# uDC_module.net
KiCad netlist of a schematic drawn in EAGLE
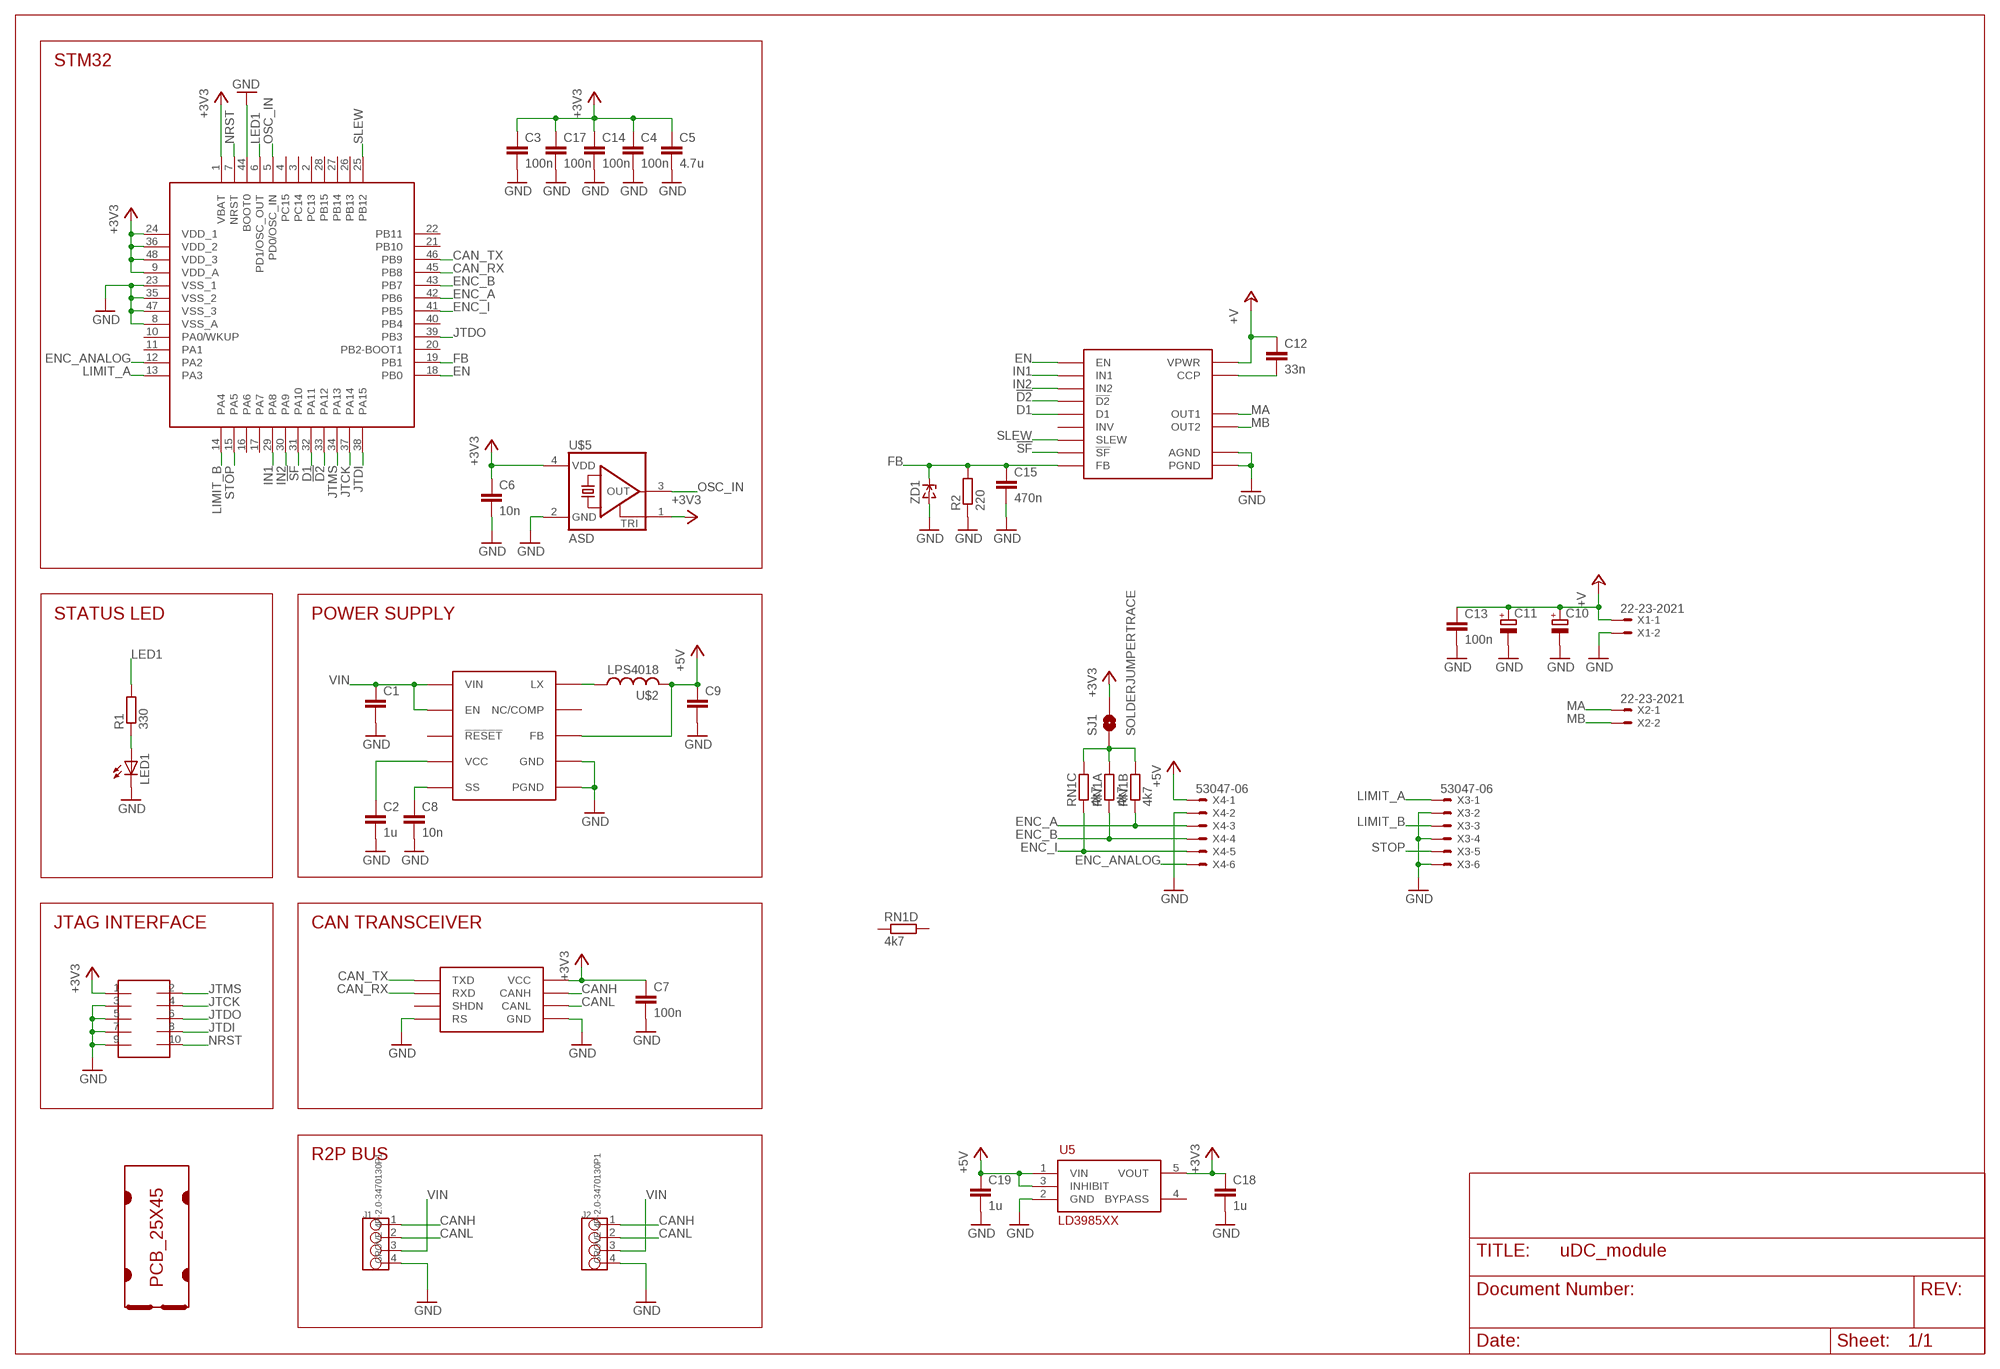
[diagram p0: schematic, sheet 1]

(export (version "E")
  (design (tool "Eeschema 10.0.6"))
  (components
    (comp (ref "C1")
      (value "C-EUC1206")
      (footprint "eagle-import:C1206")
      (libsource (lib "eagle-import") (part "C-EUC1206"))
    )
    (comp (ref "C2")
      (value "1u")
      (footprint "eagle-import:C0603")
      (libsource (lib "eagle-import") (part "C-EUC0603"))
    )
    (comp (ref "C3")
      (value "100n")
      (footprint "eagle-import:C0603")
      (libsource (lib "eagle-import") (part "C-EUC0603"))
    )
    (comp (ref "C4")
      (value "100n")
      (footprint "eagle-import:C0603")
      (libsource (lib "eagle-import") (part "C-EUC0603"))
    )
    (comp (ref "C5")
      (value "4.7u")
      (footprint "eagle-import:C0805")
      (libsource (lib "eagle-import") (part "C-EUC0805"))
    )
    (comp (ref "C6")
      (value "10n")
      (footprint "eagle-import:C0603")
      (libsource (lib "eagle-import") (part "C-EUC0603"))
    )
    (comp (ref "C7")
      (value "100n")
      (footprint "eagle-import:C0603")
      (libsource (lib "eagle-import") (part "C-EUC0603"))
    )
    (comp (ref "C8")
      (value "10n")
      (footprint "eagle-import:C0603")
      (libsource (lib "eagle-import") (part "C-EUC0603"))
    )
    (comp (ref "C9")
      (value "C-EUC0805")
      (footprint "eagle-import:C0805")
      (libsource (lib "eagle-import") (part "C-EUC0805"))
    )
    (comp (ref "C10")
      (value "CPOL-EUD")
      (footprint "eagle-import:PANASONIC_D")
      (libsource (lib "eagle-import") (part "CPOL-EUD"))
    )
    (comp (ref "C11")
      (value "CPOL-EUD")
      (footprint "eagle-import:PANASONIC_D")
      (libsource (lib "eagle-import") (part "CPOL-EUD"))
    )
    (comp (ref "C12")
      (value "33n")
      (footprint "eagle-import:C0603")
      (libsource (lib "eagle-import") (part "C-EUC0603"))
    )
    (comp (ref "C13")
      (value "100n")
      (footprint "eagle-import:C0603")
      (libsource (lib "eagle-import") (part "C-EUC0603"))
    )
    (comp (ref "C14")
      (value "100n")
      (footprint "eagle-import:C0603")
      (libsource (lib "eagle-import") (part "C-EUC0603"))
    )
    (comp (ref "C15")
      (value "470n")
      (footprint "eagle-import:C0603")
      (libsource (lib "eagle-import") (part "C-EUC0603"))
    )
    (comp (ref "C17")
      (value "100n")
      (footprint "eagle-import:C0603")
      (libsource (lib "eagle-import") (part "C-EUC0603"))
    )
    (comp (ref "C18")
      (value "1u")
      (footprint "eagle-import:C0603")
      (libsource (lib "eagle-import") (part "C-EUC0603"))
    )
    (comp (ref "C19")
      (value "1u")
      (footprint "eagle-import:C0603")
      (libsource (lib "eagle-import") (part "C-EUC0603"))
    )
    (comp (ref "J1")
      (value "GROVE-4P-2.0-3470130P1")
      (footprint "eagle-import:4P-2.0")
      (libsource (lib "eagle-import") (part "GROVE-4P-2.0-3470130P1"))
    )
    (comp (ref "J2")
      (value "GROVE-4P-2.0-3470130P1")
      (footprint "eagle-import:4P-2.0")
      (libsource (lib "eagle-import") (part "GROVE-4P-2.0-3470130P1"))
    )
    (comp (ref "LED1")
      (value "LEDCHIPLED_0805")
      (footprint "eagle-import:CHIPLED_0805")
      (libsource (lib "eagle-import") (part "LEDCHIPLED_0805"))
    )
    (comp (ref "R1")
      (value "330")
      (footprint "eagle-import:R0603")
      (libsource (lib "eagle-import") (part "R-EU_R0603"))
    )
    (comp (ref "R2")
      (value "220")
      (footprint "eagle-import:R0603")
      (libsource (lib "eagle-import") (part "R-EU_R0603"))
    )
    (comp (ref "RN1")
      (value "4k7")
      (footprint "eagle-import:RN8P-4R-CRA06S")
      (libsource (lib "eagle-import") (part "RESISTOR_ARRAY_4"))
    )
    (comp (ref "SJ1")
      (value "SOLDERJUMPERTRACE")
      (footprint "eagle-import:SJ_2S-TRACE")
      (libsource (lib "eagle-import") (part "SOLDERJUMPERTRACE"))
    )
    (comp (ref "SOT1")
      (value "MAX3051EKA")
      (footprint "eagle-import:SOT23-8L")
      (libsource (lib "eagle-import") (part "MAX3051EKA"))
    )
    (comp (ref "U$1")
      (value "PCB_25X45")
      (footprint "eagle-import:25X45")
      (libsource (lib "eagle-import") (part "PCB_25X45"))
    )
    (comp (ref "U$2")
      (value "LPS4018")
      (footprint "eagle-import:LPS4018")
      (libsource (lib "eagle-import") (part "LPS4018"))
    )
    (comp (ref "U$3")
      (value "MAX17501")
      (footprint "eagle-import:TDFN-10")
      (libsource (lib "eagle-import") (part "MAX17501"))
    )
    (comp (ref "U$4")
      (value "FTSH-105TH")
      (footprint "eagle-import:FTSH-105-TH")
      (libsource (lib "eagle-import") (part "FTSH-105TH"))
    )
    (comp (ref "U$5")
      (value "ASD")
      (footprint "eagle-import:2.5X2")
      (libsource (lib "eagle-import") (part "ASD"))
    )
    (comp (ref "U$6")
      (value "STM32F103CXTX")
      (footprint "eagle-import:LQFP48")
      (libsource (lib "eagle-import") (part "STM32F103CXTX"))
    )
    (comp (ref "U$7")
      (value "MC33962")
      (footprint "eagle-import:PQFN32")
      (libsource (lib "eagle-import") (part "MC33962"))
    )
    (comp (ref "U5")
      (value "LD3985XX")
      (footprint "eagle-import:SOT23-5L")
      (libsource (lib "eagle-import") (part "LD3985XX"))
    )
    (comp (ref "X1")
      (value "22-23-2021")
      (footprint "eagle-import:22-23-2021")
      (fields (field (name "MF") "MOLEX"))
      (libsource (lib "eagle-import") (part "22-23-2021"))
    )
    (comp (ref "X2")
      (value "22-23-2021")
      (footprint "eagle-import:22-23-2021")
      (fields (field (name "MF") "MOLEX"))
      (libsource (lib "eagle-import") (part "22-23-2021"))
    )
    (comp (ref "X3")
      (value "53047-06")
      (footprint "eagle-import:53047-06")
      (fields (field (name "MPN") "53047-0610-C"))
      (libsource (lib "eagle-import") (part "53?-06047"))
    )
    (comp (ref "X4")
      (value "53047-06")
      (footprint "eagle-import:53047-06")
      (fields (field (name "MPN") "53047-0610-C"))
      (libsource (lib "eagle-import") (part "53?-06047"))
    )
    (comp (ref "ZD1")
      (value "ZENERSOD-323F")
      (footprint "eagle-import:SOD-323F")
      (libsource (lib "eagle-import") (part "ZENERSOD-323F"))
    )
  )
  (nets
    (net (code "1") (name "+3V3") (class "Default")
      (node (ref "C14") (pin "1") (pinfunction "1_1") (pintype "passive"))
      (node (ref "C17") (pin "1") (pinfunction "1_1") (pintype "passive"))
      (node (ref "C18") (pin "1") (pinfunction "1_1") (pintype "passive"))
      (node (ref "C3") (pin "1") (pinfunction "1_1") (pintype "passive"))
      (node (ref "C4") (pin "1") (pinfunction "1_1") (pintype "passive"))
      (node (ref "C5") (pin "1") (pinfunction "1_1") (pintype "passive"))
      (node (ref "C6") (pin "1") (pinfunction "1_1") (pintype "passive"))
      (node (ref "C7") (pin "1") (pinfunction "1_1") (pintype "passive"))
      (node (ref "SJ1") (pin "2") (pinfunction "2_2") (pintype "passive"))
      (node (ref "SOT1") (pin "3") (pinfunction "VCC_3") (pintype "bidirectional"))
      (node (ref "U$4") (pin "1") (pinfunction "P$1_1") (pintype "bidirectional"))
      (node (ref "U$5") (pin "1") (pinfunction "TRI_1") (pintype "input"))
      (node (ref "U$5") (pin "4") (pinfunction "VDD_4") (pintype "power_in"))
      (node (ref "U$6") (pin "1") (pinfunction "VBAT_1") (pintype "bidirectional"))
      (node (ref "U$6") (pin "24") (pinfunction "VDD_1_24") (pintype "bidirectional"))
      (node (ref "U$6") (pin "36") (pinfunction "VDD_2_36") (pintype "bidirectional"))
      (node (ref "U$6") (pin "48") (pinfunction "VDD_3_48") (pintype "bidirectional"))
      (node (ref "U$6") (pin "9") (pinfunction "VDD_A_9") (pintype "bidirectional"))
      (node (ref "U5") (pin "5") (pinfunction "VOUT_5") (pintype "bidirectional"))
    )
    (net (code "2") (name "+5V") (class "Default")
      (node (ref "C19") (pin "1") (pinfunction "1_1") (pintype "passive"))
      (node (ref "C9") (pin "1") (pinfunction "1_1") (pintype "passive"))
      (node (ref "U$2") (pin "P$2") (pinfunction "2_P$2") (pintype "passive"))
      (node (ref "U$3") (pin "P$5") (pinfunction "FB_P$5") (pintype "bidirectional"))
      (node (ref "U5") (pin "1") (pinfunction "VIN_1") (pintype "bidirectional"))
      (node (ref "U5") (pin "3") (pinfunction "INHIBIT_3") (pintype "bidirectional"))
      (node (ref "X4") (pin "1") (pinfunction "S_1") (pintype "passive"))
    )
    (net (code "3") (name "+V") (class "Default")
      (node (ref "C10") (pin "+") (pinfunction "+_+") (pintype "passive"))
      (node (ref "C11") (pin "+") (pinfunction "+_+") (pintype "passive"))
      (node (ref "C12") (pin "1") (pinfunction "1_1") (pintype "passive"))
      (node (ref "C13") (pin "1") (pinfunction "1_1") (pintype "passive"))
      (node (ref "U$7") (pin "P$11") (pinfunction "VPWR_P$11") (pintype "bidirectional"))
      (node (ref "U$7") (pin "P$31") (pinfunction "VPWR_P$31") (pintype "bidirectional"))
      (node (ref "U$7") (pin "P$4") (pinfunction "VPWR_P$4") (pintype "bidirectional"))
      (node (ref "U$7") (pin "P$6") (pinfunction "VPWR_P$6") (pintype "bidirectional"))
      (node (ref "X1") (pin "1") (pinfunction "S_1") (pintype "passive"))
    )
    (net (code "4") (name "/CANH") (class "Default")
      (node (ref "J1") (pin "1") (pinfunction "1_1") (pintype "bidirectional"))
      (node (ref "J2") (pin "1") (pinfunction "1_1") (pintype "bidirectional"))
      (node (ref "SOT1") (pin "7") (pinfunction "CANH_7") (pintype "bidirectional"))
    )
    (net (code "5") (name "/CANL") (class "Default")
      (node (ref "J1") (pin "2") (pinfunction "2_2") (pintype "bidirectional"))
      (node (ref "J2") (pin "2") (pinfunction "2_2") (pintype "bidirectional"))
      (node (ref "SOT1") (pin "6") (pinfunction "CANL_6") (pintype "bidirectional"))
    )
    (net (code "6") (name "/CAN_RX") (class "Default")
      (node (ref "SOT1") (pin "4") (pinfunction "RXD_4") (pintype "bidirectional"))
      (node (ref "U$6") (pin "45") (pinfunction "PB8_45") (pintype "bidirectional"))
    )
    (net (code "7") (name "/CAN_TX") (class "Default")
      (node (ref "SOT1") (pin "1") (pinfunction "TXD_1") (pintype "bidirectional"))
      (node (ref "U$6") (pin "46") (pinfunction "PB9_46") (pintype "bidirectional"))
    )
    (net (code "8") (name "/D1") (class "Default")
      (node (ref "U$6") (pin "32") (pinfunction "PA11_32") (pintype "bidirectional"))
      (node (ref "U$7") (pin "P$26") (pinfunction "D1_P$26") (pintype "bidirectional"))
    )
    (net (code "9") (name "/EN") (class "Default")
      (node (ref "U$6") (pin "18") (pinfunction "PB0_18") (pintype "bidirectional"))
      (node (ref "U$7") (pin "P$10") (pinfunction "EN_P$10") (pintype "bidirectional"))
    )
    (net (code "10") (name "/ENC_A") (class "Default")
      (node (ref "RN1") (pin "2") (pinfunction "1_2") (pintype "passive"))
      (node (ref "U$6") (pin "42") (pinfunction "PB6_42") (pintype "bidirectional"))
      (node (ref "X4") (pin "3") (pinfunction "S_3") (pintype "passive"))
    )
    (net (code "11") (name "/ENC_ANALOG") (class "Default")
      (node (ref "U$6") (pin "12") (pinfunction "PA2_12") (pintype "bidirectional"))
      (node (ref "X4") (pin "6") (pinfunction "S_6") (pintype "passive"))
    )
    (net (code "12") (name "/ENC_B") (class "Default")
      (node (ref "RN1") (pin "1") (pinfunction "1_1") (pintype "passive"))
      (node (ref "U$6") (pin "43") (pinfunction "PB7_43") (pintype "bidirectional"))
      (node (ref "X4") (pin "4") (pinfunction "S_4") (pintype "passive"))
    )
    (net (code "13") (name "/ENC_I") (class "Default")
      (node (ref "RN1") (pin "3") (pinfunction "1_3") (pintype "passive"))
      (node (ref "U$6") (pin "41") (pinfunction "PB5_41") (pintype "bidirectional"))
      (node (ref "X4") (pin "5") (pinfunction "S_5") (pintype "passive"))
    )
    (net (code "14") (name "/FB") (class "Default")
      (node (ref "C15") (pin "1") (pinfunction "1_1") (pintype "passive"))
      (node (ref "R2") (pin "2") (pinfunction "2_2") (pintype "passive"))
      (node (ref "U$6") (pin "19") (pinfunction "PB1_19") (pintype "bidirectional"))
      (node (ref "U$7") (pin "P$8") (pinfunction "FB_P$8") (pintype "bidirectional"))
      (node (ref "ZD1") (pin "C") (pinfunction "C_C") (pintype "passive"))
    )
    (net (code "15") (name "/IN1") (class "Default")
      (node (ref "U$6") (pin "29") (pinfunction "PA8_29") (pintype "bidirectional"))
      (node (ref "U$7") (pin "P$2") (pinfunction "IN1_P$2") (pintype "bidirectional"))
    )
    (net (code "16") (name "/IN2") (class "Default")
      (node (ref "U$6") (pin "30") (pinfunction "PA9_30") (pintype "bidirectional"))
      (node (ref "U$7") (pin "P$1") (pinfunction "IN2_P$1") (pintype "bidirectional"))
    )
    (net (code "17") (name "/JTCK") (class "Default")
      (node (ref "U$4") (pin "4") (pinfunction "P$4_4") (pintype "bidirectional"))
      (node (ref "U$6") (pin "37") (pinfunction "PA14_37") (pintype "bidirectional"))
    )
    (net (code "18") (name "/JTDI") (class "Default")
      (node (ref "U$4") (pin "8") (pinfunction "P$8_8") (pintype "bidirectional"))
      (node (ref "U$6") (pin "38") (pinfunction "PA15_38") (pintype "bidirectional"))
    )
    (net (code "19") (name "/JTDO") (class "Default")
      (node (ref "U$4") (pin "6") (pinfunction "P$6_6") (pintype "bidirectional"))
      (node (ref "U$6") (pin "39") (pinfunction "PB3_39") (pintype "bidirectional"))
    )
    (net (code "20") (name "/JTMS") (class "Default")
      (node (ref "U$4") (pin "2") (pinfunction "P$2_2") (pintype "bidirectional"))
      (node (ref "U$6") (pin "34") (pinfunction "PA13_34") (pintype "bidirectional"))
    )
    (net (code "21") (name "/LED1") (class "Default")
      (node (ref "R1") (pin "2") (pinfunction "2_2") (pintype "passive"))
      (node (ref "U$6") (pin "6") (pinfunction "PD1/OSC_OUT_6") (pintype "bidirectional"))
    )
    (net (code "22") (name "/LIMIT_A") (class "Default")
      (node (ref "U$6") (pin "13") (pinfunction "PA3_13") (pintype "bidirectional"))
      (node (ref "X3") (pin "1") (pinfunction "S_1") (pintype "passive"))
    )
    (net (code "23") (name "/LIMIT_B") (class "Default")
      (node (ref "U$6") (pin "14") (pinfunction "PA4_14") (pintype "bidirectional"))
      (node (ref "X3") (pin "3") (pinfunction "S_3") (pintype "passive"))
    )
    (net (code "24") (name "/MA") (class "Default")
      (node (ref "U$7") (pin "P$12") (pinfunction "OUT1_P$12") (pintype "bidirectional"))
      (node (ref "U$7") (pin "P$13") (pinfunction "OUT1_P$13") (pintype "bidirectional"))
      (node (ref "U$7") (pin "P$14") (pinfunction "OUT1_P$14") (pintype "bidirectional"))
      (node (ref "U$7") (pin "P$15") (pinfunction "OUT1_P$15") (pintype "bidirectional"))
      (node (ref "X2") (pin "1") (pinfunction "S_1") (pintype "passive"))
    )
    (net (code "25") (name "/MB") (class "Default")
      (node (ref "U$7") (pin "P$27") (pinfunction "OUT2_P$27") (pintype "bidirectional"))
      (node (ref "U$7") (pin "P$28") (pinfunction "OUT2_P$28") (pintype "bidirectional"))
      (node (ref "U$7") (pin "P$29") (pinfunction "OUT2_P$29") (pintype "bidirectional"))
      (node (ref "U$7") (pin "P$30") (pinfunction "OUT2_P$30") (pintype "bidirectional"))
      (node (ref "X2") (pin "2") (pinfunction "S_2") (pintype "passive"))
    )
    (net (code "26") (name "/NRST") (class "Default")
      (node (ref "U$4") (pin "10") (pinfunction "P$10_10") (pintype "bidirectional"))
      (node (ref "U$6") (pin "7") (pinfunction "NRST_7") (pintype "bidirectional"))
    )
    (net (code "27") (name "/OSC_IN") (class "Default")
      (node (ref "U$5") (pin "3") (pinfunction "OUT_3") (pintype "output"))
      (node (ref "U$6") (pin "5") (pinfunction "PD0/OSC_IN_5") (pintype "bidirectional"))
    )
    (net (code "28") (name "/SLEW") (class "Default")
      (node (ref "U$6") (pin "25") (pinfunction "PB12_25") (pintype "bidirectional"))
      (node (ref "U$7") (pin "P$3") (pinfunction "SLEW_P$3") (pintype "bidirectional"))
    )
    (net (code "29") (name "/STOP") (class "Default")
      (node (ref "U$6") (pin "15") (pinfunction "PA5_15") (pintype "bidirectional"))
      (node (ref "X3") (pin "5") (pinfunction "S_5") (pintype "passive"))
    )
    (net (code "30") (name "/VIN") (class "Default")
      (node (ref "C1") (pin "1") (pinfunction "1_1") (pintype "passive"))
      (node (ref "J1") (pin "3") (pinfunction "3_3") (pintype "bidirectional"))
      (node (ref "J2") (pin "3") (pinfunction "3_3") (pintype "bidirectional"))
      (node (ref "U$3") (pin "P$2") (pinfunction "VIN_P$2") (pintype "bidirectional"))
      (node (ref "U$3") (pin "P$3") (pinfunction "EN_P$3") (pintype "bidirectional"))
    )
    (net (code "31") (name "/~{D2}") (class "Default")
      (node (ref "U$6") (pin "33") (pinfunction "PA12_33") (pintype "bidirectional"))
      (node (ref "U$7") (pin "P$16") (pinfunction "~{D2}_P$16") (pintype "bidirectional"))
    )
    (net (code "32") (name "/~{SF}") (class "Default")
      (node (ref "U$6") (pin "31") (pinfunction "PA10_31") (pintype "bidirectional"))
      (node (ref "U$7") (pin "P$21") (pinfunction "~{SF}_P$21") (pintype "bidirectional"))
    )
    (net (code "33") (name "GND") (class "Default")
      (node (ref "C1") (pin "2") (pinfunction "2_2") (pintype "passive"))
      (node (ref "C10") (pin "-") (pinfunction "-_-") (pintype "passive"))
      (node (ref "C11") (pin "-") (pinfunction "-_-") (pintype "passive"))
      (node (ref "C13") (pin "2") (pinfunction "2_2") (pintype "passive"))
      (node (ref "C14") (pin "2") (pinfunction "2_2") (pintype "passive"))
      (node (ref "C15") (pin "2") (pinfunction "2_2") (pintype "passive"))
      (node (ref "C17") (pin "2") (pinfunction "2_2") (pintype "passive"))
      (node (ref "C18") (pin "2") (pinfunction "2_2") (pintype "passive"))
      (node (ref "C19") (pin "2") (pinfunction "2_2") (pintype "passive"))
      (node (ref "C2") (pin "2") (pinfunction "2_2") (pintype "passive"))
      (node (ref "C3") (pin "2") (pinfunction "2_2") (pintype "passive"))
      (node (ref "C4") (pin "2") (pinfunction "2_2") (pintype "passive"))
      (node (ref "C5") (pin "2") (pinfunction "2_2") (pintype "passive"))
      (node (ref "C6") (pin "2") (pinfunction "2_2") (pintype "passive"))
      (node (ref "C7") (pin "2") (pinfunction "2_2") (pintype "passive"))
      (node (ref "C8") (pin "2") (pinfunction "2_2") (pintype "passive"))
      (node (ref "C9") (pin "2") (pinfunction "2_2") (pintype "passive"))
      (node (ref "J1") (pin "4") (pinfunction "4_4") (pintype "bidirectional"))
      (node (ref "J2") (pin "4") (pinfunction "4_4") (pintype "bidirectional"))
      (node (ref "LED1") (pin "C") (pinfunction "C_C") (pintype "passive"))
      (node (ref "R2") (pin "1") (pinfunction "1_1") (pintype "passive"))
      (node (ref "SOT1") (pin "2") (pinfunction "GND_2") (pintype "bidirectional"))
      (node (ref "SOT1") (pin "8") (pinfunction "RS_8") (pintype "bidirectional"))
      (node (ref "U$3") (pin "P$1") (pinfunction "PGND_P$1") (pintype "bidirectional"))
      (node (ref "U$3") (pin "P$11") (pinfunction "PGND_P$11") (pintype "bidirectional"))
      (node (ref "U$3") (pin "P$9") (pinfunction "GND_P$9") (pintype "bidirectional"))
      (node (ref "U$4") (pin "3") (pinfunction "P$3_3") (pintype "bidirectional"))
      (node (ref "U$4") (pin "5") (pinfunction "P$5_5") (pintype "bidirectional"))
      (node (ref "U$4") (pin "7") (pinfunction "P$7_7") (pintype "bidirectional"))
      (node (ref "U$4") (pin "9") (pinfunction "P$9_9") (pintype "bidirectional"))
      (node (ref "U$5") (pin "2") (pinfunction "GND_2") (pintype "power_in"))
      (node (ref "U$6") (pin "23") (pinfunction "VSS_1_23") (pintype "bidirectional"))
      (node (ref "U$6") (pin "35") (pinfunction "VSS_2_35") (pintype "bidirectional"))
      (node (ref "U$6") (pin "44") (pinfunction "BOOT0_44") (pintype "bidirectional"))
      (node (ref "U$6") (pin "47") (pinfunction "VSS_3_47") (pintype "bidirectional"))
      (node (ref "U$6") (pin "8") (pinfunction "VSS_A_8") (pintype "bidirectional"))
      (node (ref "U$7") (pin "P$18") (pinfunction "PGND_P$18") (pintype "bidirectional"))
      (node (ref "U$7") (pin "P$19") (pinfunction "PGND_P$19") (pintype "bidirectional"))
      (node (ref "U$7") (pin "P$20") (pinfunction "PGND_P$20") (pintype "bidirectional"))
      (node (ref "U$7") (pin "P$22") (pinfunction "PGND_P$22") (pintype "bidirectional"))
      (node (ref "U$7") (pin "P$23") (pinfunction "PGND_P$23") (pintype "bidirectional"))
      (node (ref "U$7") (pin "P$24") (pinfunction "PGND_P$24") (pintype "bidirectional"))
      (node (ref "U$7") (pin "P$33") (pinfunction "AGND_P$33") (pintype "bidirectional"))
      (node (ref "U$7") (pin "P$5") (pinfunction "AGND_P$5") (pintype "bidirectional"))
      (node (ref "U5") (pin "2") (pinfunction "GND_2") (pintype "bidirectional"))
      (node (ref "X1") (pin "2") (pinfunction "S_2") (pintype "passive"))
      (node (ref "X3") (pin "2") (pinfunction "S_2") (pintype "passive"))
      (node (ref "X3") (pin "4") (pinfunction "S_4") (pintype "passive"))
      (node (ref "X3") (pin "6") (pinfunction "S_6") (pintype "passive"))
      (node (ref "X4") (pin "2") (pinfunction "S_2") (pintype "passive"))
      (node (ref "ZD1") (pin "A") (pinfunction "A_A") (pintype "passive"))
    )
    (net (code "34") (name "Net-(LED1-PadA)") (class "Default")
      (node (ref "LED1") (pin "A") (pinfunction "A_A") (pintype "passive"))
      (node (ref "R1") (pin "1") (pinfunction "1_1") (pintype "passive"))
    )
    (net (code "35") (name "Net-(RN1A-2)") (class "Default")
      (node (ref "RN1") (pin "6") (pinfunction "2_6") (pintype "passive"))
      (node (ref "RN1") (pin "7") (pinfunction "2_7") (pintype "passive"))
      (node (ref "RN1") (pin "8") (pinfunction "2_8") (pintype "passive"))
      (node (ref "SJ1") (pin "1") (pinfunction "1_1") (pintype "passive"))
    )
    (net (code "36") (name "Net-(U$2-1)") (class "Default")
      (node (ref "U$2") (pin "P$1") (pinfunction "1_P$1") (pintype "passive"))
      (node (ref "U$3") (pin "P$10") (pinfunction "LX_P$10") (pintype "bidirectional"))
    )
    (net (code "37") (name "Net-(U$3-SS)") (class "Default")
      (node (ref "C8") (pin "1") (pinfunction "1_1") (pintype "passive"))
      (node (ref "U$3") (pin "P$6") (pinfunction "SS_P$6") (pintype "bidirectional"))
    )
    (net (code "38") (name "Net-(U$3-VCC)") (class "Default")
      (node (ref "C2") (pin "1") (pinfunction "1_1") (pintype "passive"))
      (node (ref "U$3") (pin "P$4") (pinfunction "VCC_P$4") (pintype "bidirectional"))
    )
    (net (code "39") (name "Net-(U$7-CCP)") (class "Default")
      (node (ref "C12") (pin "2") (pinfunction "2_2") (pintype "passive"))
      (node (ref "U$7") (pin "P$32") (pinfunction "CCP_P$32") (pintype "bidirectional"))
    )
    (net (code "40") (name "unconnected-(RN1D-1-Pad4)") (class "Default")
      (node (ref "RN1") (pin "4") (pinfunction "1_4") (pintype "passive"))
    )
    (net (code "41") (name "unconnected-(RN1D-2-Pad5)") (class "Default")
      (node (ref "RN1") (pin "5") (pinfunction "2_5") (pintype "passive"))
    )
    (net (code "42") (name "unconnected-(SOT1-SHDN-Pad5)") (class "Default")
      (node (ref "SOT1") (pin "5") (pinfunction "SHDN_5") (pintype "bidirectional"))
    )
    (net (code "43") (name "unconnected-(U$3-NC{slash}COMP-PadP$7)") (class "Default")
      (node (ref "U$3") (pin "P$7") (pinfunction "NC/COMP_P$7") (pintype "bidirectional"))
    )
    (net (code "44") (name "unconnected-(U$3-~{RESET}-PadP$8)") (class "Default")
      (node (ref "U$3") (pin "P$8") (pinfunction "~{RESET}_P$8") (pintype "bidirectional"))
    )
    (net (code "45") (name "unconnected-(U$6-PA0{slash}WKUP-Pad10)") (class "Default")
      (node (ref "U$6") (pin "10") (pinfunction "PA0/WKUP_10") (pintype "bidirectional"))
    )
    (net (code "46") (name "unconnected-(U$6-PA1-Pad11)") (class "Default")
      (node (ref "U$6") (pin "11") (pinfunction "PA1_11") (pintype "bidirectional"))
    )
    (net (code "47") (name "unconnected-(U$6-PA6-Pad16)") (class "Default")
      (node (ref "U$6") (pin "16") (pinfunction "PA6_16") (pintype "bidirectional"))
    )
    (net (code "48") (name "unconnected-(U$6-PA7-Pad17)") (class "Default")
      (node (ref "U$6") (pin "17") (pinfunction "PA7_17") (pintype "bidirectional"))
    )
    (net (code "49") (name "unconnected-(U$6-PB2-BOOT1-Pad20)") (class "Default")
      (node (ref "U$6") (pin "20") (pinfunction "PB2-BOOT1_20") (pintype "bidirectional"))
    )
    (net (code "50") (name "unconnected-(U$6-PB4-Pad40)") (class "Default")
      (node (ref "U$6") (pin "40") (pinfunction "PB4_40") (pintype "bidirectional"))
    )
    (net (code "51") (name "unconnected-(U$6-PB10-Pad21)") (class "Default")
      (node (ref "U$6") (pin "21") (pinfunction "PB10_21") (pintype "bidirectional"))
    )
    (net (code "52") (name "unconnected-(U$6-PB11-Pad22)") (class "Default")
      (node (ref "U$6") (pin "22") (pinfunction "PB11_22") (pintype "bidirectional"))
    )
    (net (code "53") (name "unconnected-(U$6-PB13-Pad26)") (class "Default")
      (node (ref "U$6") (pin "26") (pinfunction "PB13_26") (pintype "bidirectional"))
    )
    (net (code "54") (name "unconnected-(U$6-PB14-Pad27)") (class "Default")
      (node (ref "U$6") (pin "27") (pinfunction "PB14_27") (pintype "bidirectional"))
    )
    (net (code "55") (name "unconnected-(U$6-PB15-Pad28)") (class "Default")
      (node (ref "U$6") (pin "28") (pinfunction "PB15_28") (pintype "bidirectional"))
    )
    (net (code "56") (name "unconnected-(U$6-PC13-Pad2)") (class "Default")
      (node (ref "U$6") (pin "2") (pinfunction "PC13_2") (pintype "bidirectional"))
    )
    (net (code "57") (name "unconnected-(U$6-PC14-Pad3)") (class "Default")
      (node (ref "U$6") (pin "3") (pinfunction "PC14_3") (pintype "bidirectional"))
    )
    (net (code "58") (name "unconnected-(U$6-PC15-Pad4)") (class "Default")
      (node (ref "U$6") (pin "4") (pinfunction "PC15_4") (pintype "bidirectional"))
    )
    (net (code "59") (name "unconnected-(U$7-INV-PadP$7)") (class "Default")
      (node (ref "U$7") (pin "P$7") (pinfunction "INV_P$7") (pintype "bidirectional"))
    )
    (net (code "60") (name "unconnected-(U5-BYPASS-Pad4)") (class "Default")
      (node (ref "U5") (pin "4") (pinfunction "BYPASS_4") (pintype "bidirectional"))
    )
  )
)
